# 4_DIGIT_7_SEGMENT.net
KiCad netlist of a schematic drawn in Altium Designer
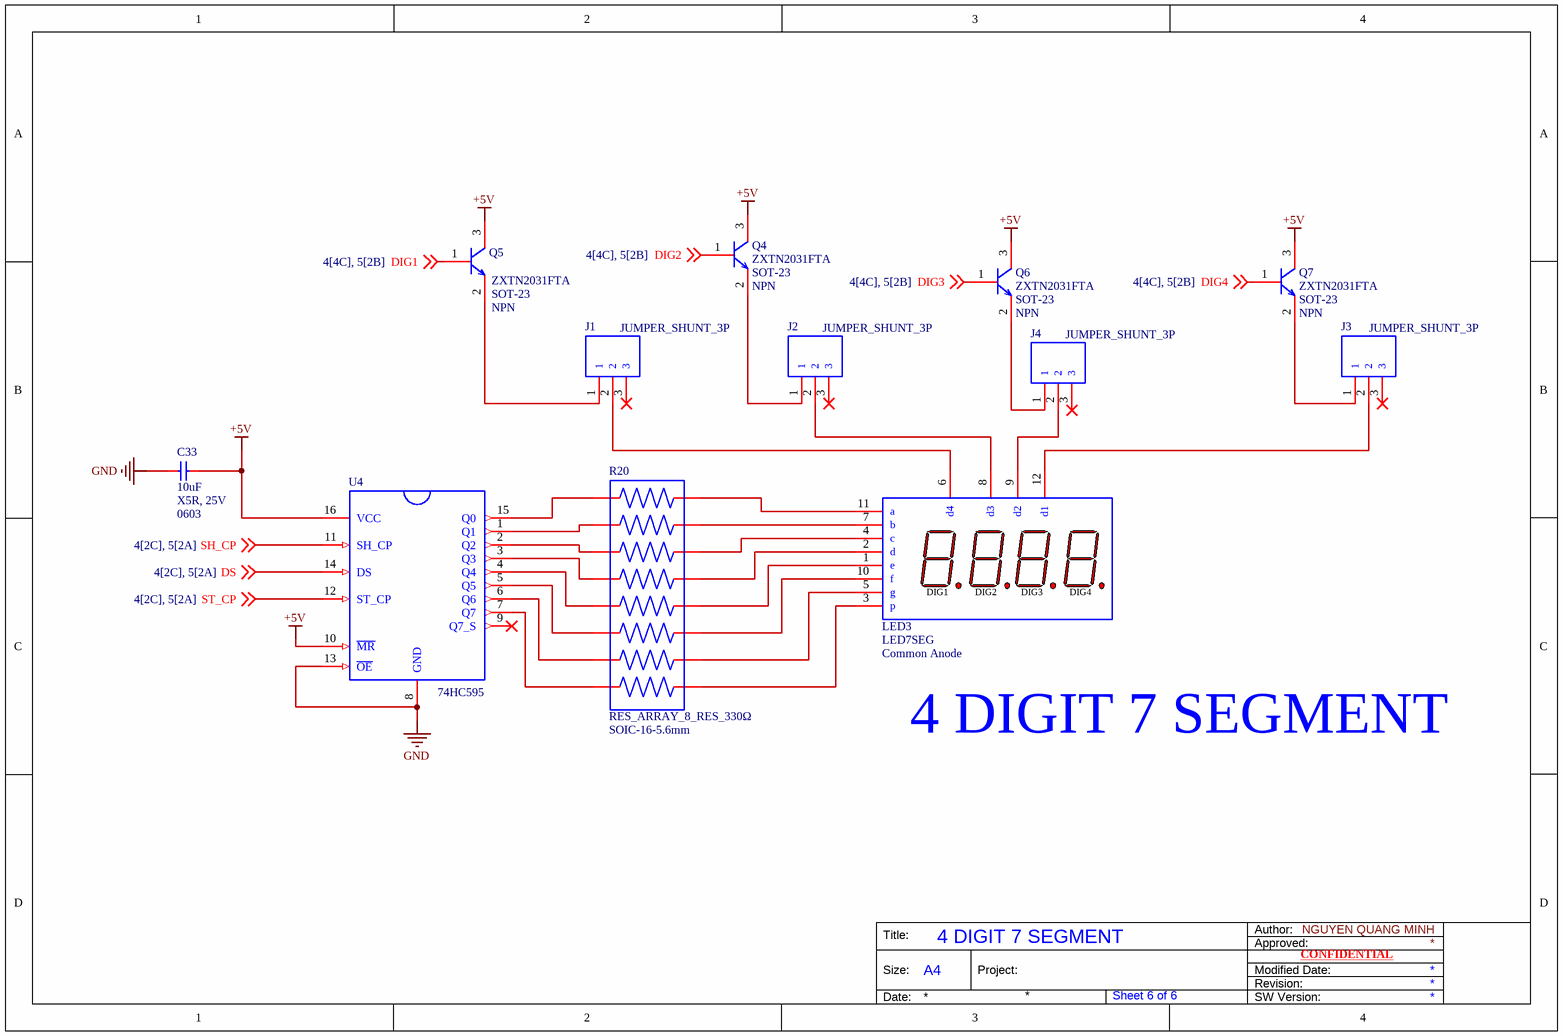
[diagram p0: 4 DIGIT 7 SEGMENT.SchDoc]

(export (version "E")
  (design (tool "Eeschema 10.0.6"))
  (components
    (comp (ref "C33")
      (value "10uF")
      (footprint "C0603")
      (description "25V 10uF X5R ±20% 0603 Multilayer Ceramic Capacitors MLCC - SMD/SMT ROHS")
      (fields
        (field (name "MANUFACTURER") "YAGEO")
        (field (name "MFR. PART") "CC0603MRX5R8BB106")
        (field (name "TEMPERATURE COEFFICIENT") "X5R, 25V")
        (field (name "PACKAGE") "0603")
      )
      (libsource (lib "Capacitor") (part "C0603_MLCC_10uF_X5R_25V"))
    )
    (comp (ref "J1")
      (value "JUMPER_SHUNT_3P")
      (footprint "JUMPER_SHUNT_3P")
      (fields
        (field (name "MANUFACTURER") "XFCN")
        (field (name "MFR. PART") "PZ254V-11-03P")
        (field (name "LCSC PART") "C2937625")
      )
      (libsource (lib "JUMP") (part "JUMPER_SHUNT_3P"))
    )
    (comp (ref "J2")
      (value "JUMPER_SHUNT_3P")
      (footprint "JUMPER_SHUNT_3P")
      (fields
        (field (name "MANUFACTURER") "XFCN")
        (field (name "MFR. PART") "PZ254V-11-03P")
        (field (name "LCSC PART") "C2937625")
      )
      (libsource (lib "JUMP") (part "JUMPER_SHUNT_3P"))
    )
    (comp (ref "J3")
      (value "JUMPER_SHUNT_3P")
      (footprint "JUMPER_SHUNT_3P")
      (fields
        (field (name "MANUFACTURER") "XFCN")
        (field (name "MFR. PART") "PZ254V-11-03P")
        (field (name "LCSC PART") "C2937625")
      )
      (libsource (lib "JUMP") (part "JUMPER_SHUNT_3P"))
    )
    (comp (ref "J4")
      (value "JUMPER_SHUNT_3P")
      (footprint "JUMPER_SHUNT_3P")
      (fields
        (field (name "MANUFACTURER") "XFCN")
        (field (name "MFR. PART") "PZ254V-11-03P")
        (field (name "LCSC PART") "C2937625")
      )
      (libsource (lib "JUMP") (part "JUMPER_SHUNT_3P"))
    )
    (comp (ref "LED3")
      (value "LED7SEG")
      (footprint "LED7SEG_4")
      (description "Red 4 Common Anode 0.56 Through Hole LED Segment Displays ROHS")
      (fields
        (field (name "MANUFACTURER") "ZHIHAO")
        (field (name "MFR. PART") "FJ5461BH")
        (field (name "LED POLARITY") "Common Anode")
      )
      (libsource (lib "LED") (part "LED7SEG_Common_Anode"))
    )
    (comp (ref "Q4")
      (value "ZXTN2031FTA")
      (footprint "SOT-23")
      (description "50V 200@2A,2V 1.2W 5A NPN SOT-23 Bipolar (BJT) ROHS")
      (fields
        (field (name "MANUFACTURER") "DIODES")
        (field (name "LCSC PART") "C92166")
        (field (name "PACKAGE") "SOT-23")
        (field (name "TYPE") "NPN")
      )
      (libsource (lib "BJT and FET") (part "ZXTN2031FTA"))
    )
    (comp (ref "Q5")
      (value "ZXTN2031FTA")
      (footprint "SOT-23")
      (description "50V 200@2A,2V 1.2W 5A NPN SOT-23 Bipolar (BJT) ROHS")
      (fields
        (field (name "MANUFACTURER") "DIODES")
        (field (name "LCSC PART") "C92166")
        (field (name "PACKAGE") "SOT-23")
        (field (name "TYPE") "NPN")
      )
      (libsource (lib "BJT and FET") (part "ZXTN2031FTA"))
    )
    (comp (ref "Q6")
      (value "ZXTN2031FTA")
      (footprint "SOT-23")
      (description "50V 200@2A,2V 1.2W 5A NPN SOT-23 Bipolar (BJT) ROHS")
      (fields
        (field (name "MANUFACTURER") "DIODES")
        (field (name "LCSC PART") "C92166")
        (field (name "PACKAGE") "SOT-23")
        (field (name "TYPE") "NPN")
      )
      (libsource (lib "BJT and FET") (part "ZXTN2031FTA"))
    )
    (comp (ref "Q7")
      (value "ZXTN2031FTA")
      (footprint "SOT-23")
      (description "50V 200@2A,2V 1.2W 5A NPN SOT-23 Bipolar (BJT) ROHS")
      (fields
        (field (name "MANUFACTURER") "DIODES")
        (field (name "LCSC PART") "C92166")
        (field (name "PACKAGE") "SOT-23")
        (field (name "TYPE") "NPN")
      )
      (libsource (lib "BJT and FET") (part "ZXTN2031FTA"))
    )
    (comp (ref "R20")
      (value "RES_ARRAY_8_RES_330Ω")
      (footprint "SOIC-16-5.6mm")
      (description "8 ±2% 330Ω 160mW ±100ppm/℃ SOIC-16-5.6mm Resistor Networks, Arrays ROHS")
      (fields
        (field (name "MANUFACTURER") "BOURNS")
        (field (name "TOLERANCE") "±2%")
        (field (name "PACKAGE") "SOIC-16-5.6mm")
      )
      (libsource (lib "Resistor") (part "RES_ARRAY_8_RES_330Ω"))
    )
    (comp (ref "U4")
      (value "74HC595")
      (footprint "TSSOP16")
      (description "8 2V~6V 1 Serial-to-Serial or Parallel TSSOP-16 Shift Registers ROHS")
      (fields (field (name "MANUFACTURER") "Nexperia") (field (name "MFR. PART") "74HC595PW,118"))
      (libsource (lib "IC") (part "74HC595"))
    )
  )
  (nets
    (net (code "1") (name "+5V") (class "Default")
      (node (ref "C33") (pin "1") (pinfunction "1_1") (pintype "passive"))
      (node (ref "Q4") (pin "3") (pinfunction "C_3") (pintype "passive"))
      (node (ref "Q5") (pin "3") (pinfunction "C_3") (pintype "passive"))
      (node (ref "Q6") (pin "3") (pinfunction "C_3") (pintype "passive"))
      (node (ref "Q7") (pin "3") (pinfunction "C_3") (pintype "passive"))
      (node (ref "U4") (pin "10") (pinfunction "~{MR}_10") (pintype "input"))
      (node (ref "U4") (pin "16") (pinfunction "VCC_16") (pintype "power_in"))
    )
    (net (code "2") (name "DIG1") (class "Default")
      (node (ref "Q5") (pin "1") (pinfunction "B_1") (pintype "passive"))
    )
    (net (code "3") (name "DIG2") (class "Default")
      (node (ref "Q4") (pin "1") (pinfunction "B_1") (pintype "passive"))
    )
    (net (code "4") (name "DIG3") (class "Default")
      (node (ref "Q6") (pin "1") (pinfunction "B_1") (pintype "passive"))
    )
    (net (code "5") (name "DIG4") (class "Default")
      (node (ref "Q7") (pin "1") (pinfunction "B_1") (pintype "passive"))
    )
    (net (code "6") (name "DS") (class "Default")
      (node (ref "U4") (pin "14") (pinfunction "DS_14") (pintype "input"))
    )
    (net (code "7") (name "GND") (class "Default")
      (node (ref "C33") (pin "2") (pinfunction "2_2") (pintype "passive"))
      (node (ref "U4") (pin "13") (pinfunction "~{OE}_13") (pintype "input"))
      (node (ref "U4") (pin "8") (pinfunction "GND_8") (pintype "passive"))
    )
    (net (code "8") (name "Net-(LED3-a)") (class "Default")
      (node (ref "LED3") (pin "11") (pinfunction "a_11") (pintype "passive"))
      (node (ref "R20") (pin "16") (pinfunction "16_16") (pintype "passive"))
    )
    (net (code "9") (name "Net-(LED3-b)") (class "Default")
      (node (ref "LED3") (pin "7") (pinfunction "b_7") (pintype "passive"))
      (node (ref "R20") (pin "15") (pinfunction "15_15") (pintype "passive"))
    )
    (net (code "10") (name "Net-(LED3-c)") (class "Default")
      (node (ref "LED3") (pin "4") (pinfunction "c_4") (pintype "passive"))
      (node (ref "R20") (pin "14") (pinfunction "14_14") (pintype "passive"))
    )
    (net (code "11") (name "Net-(LED3-d)") (class "Default")
      (node (ref "LED3") (pin "2") (pinfunction "d_2") (pintype "passive"))
      (node (ref "R20") (pin "13") (pinfunction "13_13") (pintype "passive"))
    )
    (net (code "12") (name "Net-(LED3-d1)") (class "Default")
      (node (ref "J3") (pin "2") (pinfunction "2_2") (pintype "passive"))
      (node (ref "LED3") (pin "12") (pinfunction "d1_12") (pintype "passive"))
    )
    (net (code "13") (name "Net-(LED3-d2)") (class "Default")
      (node (ref "J4") (pin "2") (pinfunction "2_2") (pintype "passive"))
      (node (ref "LED3") (pin "9") (pinfunction "d2_9") (pintype "passive"))
    )
    (net (code "14") (name "Net-(LED3-d3)") (class "Default")
      (node (ref "J2") (pin "2") (pinfunction "2_2") (pintype "passive"))
      (node (ref "LED3") (pin "8") (pinfunction "d3_8") (pintype "passive"))
    )
    (net (code "15") (name "Net-(LED3-d4)") (class "Default")
      (node (ref "J1") (pin "2") (pinfunction "2_2") (pintype "passive"))
      (node (ref "LED3") (pin "6") (pinfunction "d4_6") (pintype "passive"))
    )
    (net (code "16") (name "Net-(LED3-e)") (class "Default")
      (node (ref "LED3") (pin "1") (pinfunction "e_1") (pintype "passive"))
      (node (ref "R20") (pin "12") (pinfunction "12_12") (pintype "passive"))
    )
    (net (code "17") (name "Net-(LED3-f)") (class "Default")
      (node (ref "LED3") (pin "10") (pinfunction "f_10") (pintype "passive"))
      (node (ref "R20") (pin "11") (pinfunction "11_11") (pintype "passive"))
    )
    (net (code "18") (name "Net-(LED3-g)") (class "Default")
      (node (ref "LED3") (pin "5") (pinfunction "g_5") (pintype "passive"))
      (node (ref "R20") (pin "10") (pinfunction "10_10") (pintype "passive"))
    )
    (net (code "19") (name "Net-(LED3-p)") (class "Default")
      (node (ref "LED3") (pin "3") (pinfunction "p_3") (pintype "passive"))
      (node (ref "R20") (pin "9") (pinfunction "9_9") (pintype "passive"))
    )
    (net (code "20") (name "Net-(Q4-E)") (class "Default")
      (node (ref "J2") (pin "1") (pinfunction "1_1") (pintype "passive"))
      (node (ref "Q4") (pin "2") (pinfunction "E_2") (pintype "passive"))
    )
    (net (code "21") (name "Net-(Q5-E)") (class "Default")
      (node (ref "J1") (pin "1") (pinfunction "1_1") (pintype "passive"))
      (node (ref "Q5") (pin "2") (pinfunction "E_2") (pintype "passive"))
    )
    (net (code "22") (name "Net-(Q6-E)") (class "Default")
      (node (ref "J4") (pin "1") (pinfunction "1_1") (pintype "passive"))
      (node (ref "Q6") (pin "2") (pinfunction "E_2") (pintype "passive"))
    )
    (net (code "23") (name "Net-(Q7-E)") (class "Default")
      (node (ref "J3") (pin "1") (pinfunction "1_1") (pintype "passive"))
      (node (ref "Q7") (pin "2") (pinfunction "E_2") (pintype "passive"))
    )
    (net (code "24") (name "Net-(U4-Q0)") (class "Default")
      (node (ref "R20") (pin "1") (pinfunction "1_1") (pintype "passive"))
      (node (ref "U4") (pin "15") (pinfunction "Q0_15") (pintype "output"))
    )
    (net (code "25") (name "Net-(U4-Q1)") (class "Default")
      (node (ref "R20") (pin "2") (pinfunction "2_2") (pintype "passive"))
      (node (ref "U4") (pin "1") (pinfunction "Q1_1") (pintype "output"))
    )
    (net (code "26") (name "Net-(U4-Q2)") (class "Default")
      (node (ref "R20") (pin "3") (pinfunction "3_3") (pintype "passive"))
      (node (ref "U4") (pin "2") (pinfunction "Q2_2") (pintype "output"))
    )
    (net (code "27") (name "Net-(U4-Q3)") (class "Default")
      (node (ref "R20") (pin "4") (pinfunction "4_4") (pintype "passive"))
      (node (ref "U4") (pin "3") (pinfunction "Q3_3") (pintype "output"))
    )
    (net (code "28") (name "Net-(U4-Q4)") (class "Default")
      (node (ref "R20") (pin "5") (pinfunction "5_5") (pintype "passive"))
      (node (ref "U4") (pin "4") (pinfunction "Q4_4") (pintype "output"))
    )
    (net (code "29") (name "Net-(U4-Q5)") (class "Default")
      (node (ref "R20") (pin "6") (pinfunction "6_6") (pintype "passive"))
      (node (ref "U4") (pin "5") (pinfunction "Q5_5") (pintype "output"))
    )
    (net (code "30") (name "Net-(U4-Q6)") (class "Default")
      (node (ref "R20") (pin "7") (pinfunction "7_7") (pintype "passive"))
      (node (ref "U4") (pin "6") (pinfunction "Q6_6") (pintype "output"))
    )
    (net (code "31") (name "Net-(U4-Q7)") (class "Default")
      (node (ref "R20") (pin "8") (pinfunction "8_8") (pintype "passive"))
      (node (ref "U4") (pin "7") (pinfunction "Q7_7") (pintype "output"))
    )
    (net (code "32") (name "SH_CP") (class "Default")
      (node (ref "U4") (pin "11") (pinfunction "SH_CP_11") (pintype "input"))
    )
    (net (code "33") (name "ST_CP") (class "Default")
      (node (ref "U4") (pin "12") (pinfunction "ST_CP_12") (pintype "input"))
    )
    (net (code "34") (name "unconnected-(J1-Pad3)") (class "Default")
      (node (ref "J1") (pin "3") (pinfunction "3_3") (pintype "passive+no_connect"))
    )
    (net (code "35") (name "unconnected-(J2-Pad3)") (class "Default")
      (node (ref "J2") (pin "3") (pinfunction "3_3") (pintype "passive+no_connect"))
    )
    (net (code "36") (name "unconnected-(J3-Pad3)") (class "Default")
      (node (ref "J3") (pin "3") (pinfunction "3_3") (pintype "passive+no_connect"))
    )
    (net (code "37") (name "unconnected-(J4-Pad3)") (class "Default")
      (node (ref "J4") (pin "3") (pinfunction "3_3") (pintype "passive+no_connect"))
    )
    (net (code "38") (name "unconnected-(U4-Q7_S-Pad9)") (class "Default")
      (node (ref "U4") (pin "9") (pinfunction "Q7_S_9") (pintype "output+no_connect"))
    )
  )
)
